# sch_AGV_Header.net
KiCad netlist of a schematic drawn in Altium Designer
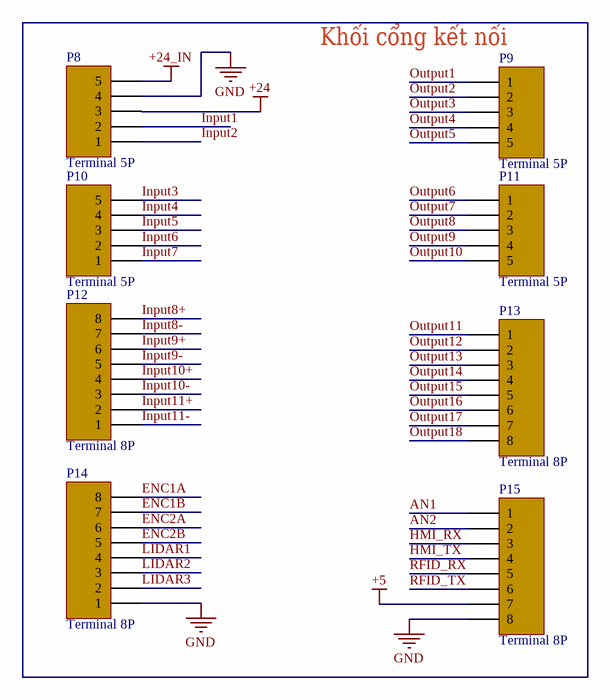
[diagram p0: sch_AGV_Header.SchDoc]

(export (version "E")
  (design (tool "Eeschema 10.0.6"))
  (components
    (comp (ref "P8")
      (value "Terminal 5P")
      (footprint "BIG_Header 5")
      (description "Terminal 5.08m")
      (fields (field (name "PUBLISHER") "Altium Limited"))
      (libsource (lib "") (part "Terminal 5P_1"))
    )
    (comp (ref "P9")
      (value "Terminal 5P")
      (footprint "BIG_Header 5")
      (description "Terminal 5.08m")
      (fields (field (name "PUBLISHER") "Altium Limited"))
      (libsource (lib "schelib_AGVcontrol") (part "Terminal 5P"))
    )
    (comp (ref "P10")
      (value "Terminal 5P")
      (footprint "BIG_Header 5")
      (description "Terminal 5.08m")
      (fields (field (name "PUBLISHER") "Altium Limited"))
      (libsource (lib "") (part "Terminal 5P_1"))
    )
    (comp (ref "P11")
      (value "Terminal 5P")
      (footprint "BIG_Header 5")
      (description "Terminal 5.08m")
      (fields (field (name "PUBLISHER") "Altium Limited"))
      (libsource (lib "schelib_AGVcontrol") (part "Terminal 5P"))
    )
    (comp (ref "P12")
      (value "Terminal 8P")
      (footprint "BIG_Header 8")
      (description "Terminal 5.08")
      (fields (field (name "PUBLISHER") "Altium Limited"))
      (libsource (lib "") (part "Terminal 8P_1"))
    )
    (comp (ref "P13")
      (value "Terminal 8P")
      (footprint "BIG_Header 8")
      (description "Terminal 5.08")
      (fields (field (name "PUBLISHER") "Altium Limited"))
      (libsource (lib "schelib_AGVcontrol") (part "Terminal 8P"))
    )
    (comp (ref "P14")
      (value "Terminal 8P")
      (footprint "BIG_Header 8")
      (description "Terminal 5.08")
      (fields (field (name "PUBLISHER") "Altium Limited"))
      (libsource (lib "") (part "Terminal 8P_1"))
    )
    (comp (ref "P15")
      (value "Terminal 8P")
      (footprint "BIG_Header 8")
      (description "Terminal 5.08")
      (fields (field (name "PUBLISHER") "Altium Limited"))
      (libsource (lib "schelib_AGVcontrol") (part "Terminal 8P"))
    )
  )
  (nets
    (net (code "1") (name "+5") (class "Default")
      (node (ref "P15") (pin "7") (pinfunction "7_7") (pintype "passive"))
    )
    (net (code "2") (name "+24") (class "Default")
      (node (ref "P8") (pin "3") (pinfunction "3_3") (pintype "passive"))
    )
    (net (code "3") (name "+24_IN") (class "Default")
      (node (ref "P8") (pin "5") (pinfunction "5_5") (pintype "passive"))
    )
    (net (code "4") (name "/AN1") (class "Default")
      (node (ref "P15") (pin "1") (pinfunction "1_1") (pintype "passive"))
    )
    (net (code "5") (name "/AN2") (class "Default")
      (node (ref "P15") (pin "2") (pinfunction "2_2") (pintype "passive"))
    )
    (net (code "6") (name "/ENC1A") (class "Default")
      (node (ref "P14") (pin "8") (pinfunction "8_8") (pintype "passive"))
    )
    (net (code "7") (name "/ENC1B") (class "Default")
      (node (ref "P14") (pin "7") (pinfunction "7_7") (pintype "passive"))
    )
    (net (code "8") (name "/ENC2A") (class "Default")
      (node (ref "P14") (pin "6") (pinfunction "6_6") (pintype "passive"))
    )
    (net (code "9") (name "/ENC2B") (class "Default")
      (node (ref "P14") (pin "5") (pinfunction "5_5") (pintype "passive"))
    )
    (net (code "10") (name "/HMI_RX") (class "Default")
      (node (ref "P15") (pin "3") (pinfunction "3_3") (pintype "passive"))
    )
    (net (code "11") (name "/HMI_TX") (class "Default")
      (node (ref "P15") (pin "4") (pinfunction "4_4") (pintype "passive"))
    )
    (net (code "12") (name "/Input1") (class "Default")
      (node (ref "P8") (pin "2") (pinfunction "2_2") (pintype "passive"))
    )
    (net (code "13") (name "/Input2") (class "Default")
      (node (ref "P8") (pin "1") (pinfunction "1_1") (pintype "passive"))
    )
    (net (code "14") (name "/Input3") (class "Default")
      (node (ref "P10") (pin "5") (pinfunction "5_5") (pintype "passive"))
    )
    (net (code "15") (name "/Input4") (class "Default")
      (node (ref "P10") (pin "4") (pinfunction "4_4") (pintype "passive"))
    )
    (net (code "16") (name "/Input5") (class "Default")
      (node (ref "P10") (pin "3") (pinfunction "3_3") (pintype "passive"))
    )
    (net (code "17") (name "/Input6") (class "Default")
      (node (ref "P10") (pin "2") (pinfunction "2_2") (pintype "passive"))
    )
    (net (code "18") (name "/Input7") (class "Default")
      (node (ref "P10") (pin "1") (pinfunction "1_1") (pintype "passive"))
    )
    (net (code "19") (name "/Input8+") (class "Default")
      (node (ref "P12") (pin "8") (pinfunction "8_8") (pintype "passive"))
    )
    (net (code "20") (name "/Input8-") (class "Default")
      (node (ref "P12") (pin "7") (pinfunction "7_7") (pintype "passive"))
    )
    (net (code "21") (name "/Input9+") (class "Default")
      (node (ref "P12") (pin "6") (pinfunction "6_6") (pintype "passive"))
    )
    (net (code "22") (name "/Input9-") (class "Default")
      (node (ref "P12") (pin "5") (pinfunction "5_5") (pintype "passive"))
    )
    (net (code "23") (name "/Input10+") (class "Default")
      (node (ref "P12") (pin "4") (pinfunction "4_4") (pintype "passive"))
    )
    (net (code "24") (name "/Input10-") (class "Default")
      (node (ref "P12") (pin "3") (pinfunction "3_3") (pintype "passive"))
    )
    (net (code "25") (name "/Input11+") (class "Default")
      (node (ref "P12") (pin "2") (pinfunction "2_2") (pintype "passive"))
    )
    (net (code "26") (name "/Input11-") (class "Default")
      (node (ref "P12") (pin "1") (pinfunction "1_1") (pintype "passive"))
    )
    (net (code "27") (name "/LIDAR1") (class "Default")
      (node (ref "P14") (pin "4") (pinfunction "4_4") (pintype "passive"))
    )
    (net (code "28") (name "/LIDAR2") (class "Default")
      (node (ref "P14") (pin "3") (pinfunction "3_3") (pintype "passive"))
    )
    (net (code "29") (name "/LIDAR3") (class "Default")
      (node (ref "P14") (pin "2") (pinfunction "2_2") (pintype "passive"))
    )
    (net (code "30") (name "/Output1") (class "Default")
      (node (ref "P9") (pin "1") (pinfunction "1_1") (pintype "passive"))
    )
    (net (code "31") (name "/Output2") (class "Default")
      (node (ref "P9") (pin "2") (pinfunction "2_2") (pintype "passive"))
    )
    (net (code "32") (name "/Output3") (class "Default")
      (node (ref "P9") (pin "3") (pinfunction "3_3") (pintype "passive"))
    )
    (net (code "33") (name "/Output4") (class "Default")
      (node (ref "P9") (pin "4") (pinfunction "4_4") (pintype "passive"))
    )
    (net (code "34") (name "/Output5") (class "Default")
      (node (ref "P9") (pin "5") (pinfunction "5_5") (pintype "passive"))
    )
    (net (code "35") (name "/Output6") (class "Default")
      (node (ref "P11") (pin "1") (pinfunction "1_1") (pintype "passive"))
    )
    (net (code "36") (name "/Output7") (class "Default")
      (node (ref "P11") (pin "2") (pinfunction "2_2") (pintype "passive"))
    )
    (net (code "37") (name "/Output8") (class "Default")
      (node (ref "P11") (pin "3") (pinfunction "3_3") (pintype "passive"))
    )
    (net (code "38") (name "/Output9") (class "Default")
      (node (ref "P11") (pin "4") (pinfunction "4_4") (pintype "passive"))
    )
    (net (code "39") (name "/Output10") (class "Default")
      (node (ref "P11") (pin "5") (pinfunction "5_5") (pintype "passive"))
    )
    (net (code "40") (name "/Output11") (class "Default")
      (node (ref "P13") (pin "1") (pinfunction "1_1") (pintype "passive"))
    )
    (net (code "41") (name "/Output12") (class "Default")
      (node (ref "P13") (pin "2") (pinfunction "2_2") (pintype "passive"))
    )
    (net (code "42") (name "/Output13") (class "Default")
      (node (ref "P13") (pin "3") (pinfunction "3_3") (pintype "passive"))
    )
    (net (code "43") (name "/Output14") (class "Default")
      (node (ref "P13") (pin "4") (pinfunction "4_4") (pintype "passive"))
    )
    (net (code "44") (name "/Output15") (class "Default")
      (node (ref "P13") (pin "5") (pinfunction "5_5") (pintype "passive"))
    )
    (net (code "45") (name "/Output16") (class "Default")
      (node (ref "P13") (pin "6") (pinfunction "6_6") (pintype "passive"))
    )
    (net (code "46") (name "/Output17") (class "Default")
      (node (ref "P13") (pin "7") (pinfunction "7_7") (pintype "passive"))
    )
    (net (code "47") (name "/Output18") (class "Default")
      (node (ref "P13") (pin "8") (pinfunction "8_8") (pintype "passive"))
    )
    (net (code "48") (name "/RFID_RX") (class "Default")
      (node (ref "P15") (pin "5") (pinfunction "5_5") (pintype "passive"))
    )
    (net (code "49") (name "/RFID_TX") (class "Default")
      (node (ref "P15") (pin "6") (pinfunction "6_6") (pintype "passive"))
    )
    (net (code "50") (name "GND") (class "Default")
      (node (ref "P14") (pin "1") (pinfunction "1_1") (pintype "passive"))
      (node (ref "P15") (pin "8") (pinfunction "8_8") (pintype "passive"))
      (node (ref "P8") (pin "4") (pinfunction "4_4") (pintype "passive"))
    )
  )
)
